# Power_Supply.net
KiCad netlist of a schematic drawn in Altium Designer
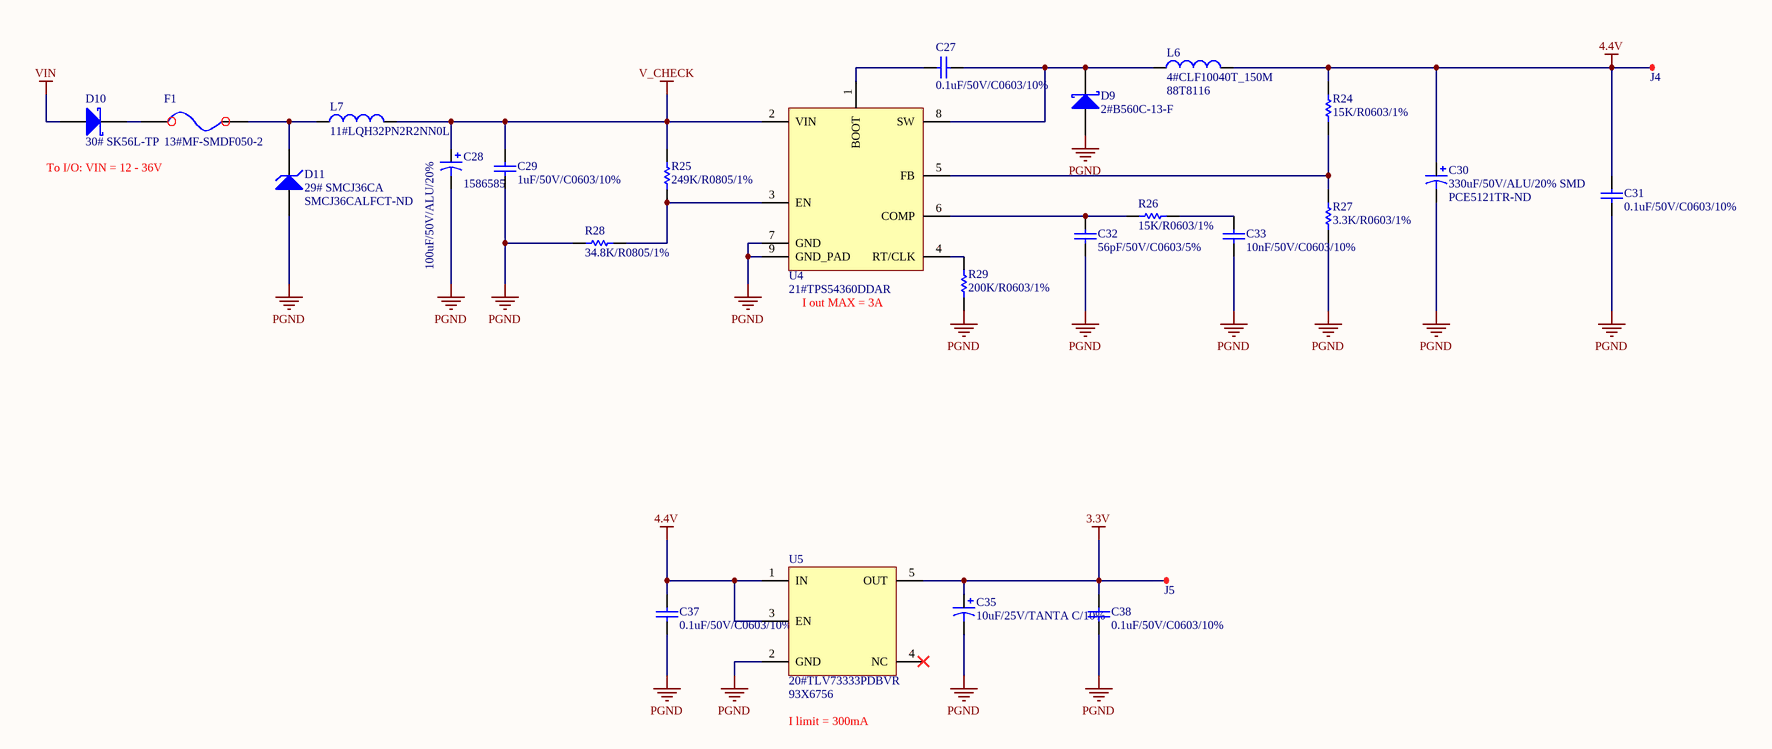
[diagram p0: Power Supply.SchDoc]

(export (version "E")
  (design (tool "Eeschema 10.0.6"))
  (components
    (comp (ref "C27")
      (value "0.1uF/50V/C0603/10%")
      (footprint "Cap Ceramic 0603 SMD")
      (description "CAP CER 0.1UF 50V 10% X7R 0603")
      (fields
        (field (name "MANUFACTURER") "Murata Electronics North America")
        (field (name "MANUFACTURER PART NUMBER") "GRM188R71H104KA93D")
      )
      (libsource (lib "GSHT_181013") (part "0.1uF/50V/C0603/10%"))
    )
    (comp (ref "C28")
      (value "100uF/50V/ALU/20%")
      (footprint "CAP ALU CASE F SMD")
      (description "CAP ALU 100UF 20% 50V RADIAL")
      (fields
        (field (name "MANUFACTURER") "Panasonic Electronic Components")
        (field (name "MANUFACTURER PART NUMBER") "ECA-1HM101B")
        (field (name "SUPPLIER PART NUMBER 1") "1586585")
      )
      (libsource (lib "GSHT_181013") (part "100uF/50V/ALU 8X11.5/20%"))
    )
    (comp (ref "C29")
      (value "1uF/50V/C0603/10%")
      (footprint "Cap Ceramic 0603 SMD")
      (description "CAP CER 1UF 50V X7R 0603")
      (fields
        (field (name "MANUFACTURER") "Samsung Electro-Mechanics America, Inc.")
        (field (name "MANUFACTURER PART NUMBER") "CL21B105KBFNNNE")
      )
      (libsource (lib "GSHT_181013") (part "1uF/50V/C0603/10%"))
    )
    (comp (ref "C30")
      (value "330uF/50V/ALU/20% SMD")
      (footprint "CAP ALU CASE G SMD")
      (description "CAP ALU 330UF 20% 50V SMD")
      (fields
        (field (name "MANUFACTURER") "Nichicon")
        (field (name "MANUFACTURER PART NUMBER") "UPW1J331MHD")
        (field (name "SUPPLIER PART NUMBER 1") "PCE5121TR-ND")
      )
      (libsource (lib "GSHT_181013") (part "330uF/50V/ALU12.5X20mm/20%/7000Hrs"))
    )
    (comp (ref "C31")
      (value "0.1uF/50V/C0603/10%")
      (footprint "Cap Ceramic 0603 SMD")
      (description "CAP CER 0.1UF 50V 10% X7R 0603")
      (fields
        (field (name "MANUFACTURER") "Murata Electronics North America")
        (field (name "MANUFACTURER PART NUMBER") "GRM188R71H104KA93D")
      )
      (libsource (lib "GSHT_181013") (part "0.1uF/50V/C0603/10%"))
    )
    (comp (ref "C32")
      (value "56pF/50V/C0603/5%")
      (footprint "Cap Ceramic 0603 SMD")
      (description "Cap Ceramic 56pF 50V C0G 5% SMD 0603 125C Paper T/R")
      (fields
        (field (name "MANUFACTURER") "Samsung")
        (field (name "MANUFACTURER PART NUMBER") "CL10C560JB8NNNC")
      )
      (libsource (lib "GSHT_181013") (part "56pF/50V/C0603/5%"))
    )
    (comp (ref "C33")
      (value "10nF/50V/C0603/10%")
      (footprint "Cap Ceramic 0603 SMD")
      (description "CAP CER 10000PF 50V X7R 0603")
      (fields
        (field (name "MANUFACTURER") "Murata Electronics North America")
        (field (name "MANUFACTURER PART NUMBER") "GRM188R71H103KA01D")
      )
      (libsource (lib "GSHT_181013") (part "10nF/50V/C0603/10%"))
    )
    (comp (ref "C35")
      (value "10uF/25V/TANTA C/10%")
      (footprint "CAP TANT CASE C SMD")
      (description "Tantalum Capacitors - Solid SMD 25v 10uF 20%Tol Code C")
      (fields
        (field (name "MANUFACTURER") "Kyocera AVX")
        (field (name "MANUFACTURER PART NUMBER") "TAJB106M025RNJ")
      )
      (libsource (lib "GSHT_181013") (part "TAJB106M025RNJ"))
    )
    (comp (ref "C37")
      (value "0.1uF/50V/C0603/10%")
      (footprint "Cap Ceramic 0603 SMD")
      (description "CAP CER 0.1UF 50V 10% X7R 0603")
      (fields
        (field (name "MANUFACTURER") "Murata Electronics North America")
        (field (name "MANUFACTURER PART NUMBER") "GRM188R71H104KA93D")
      )
      (libsource (lib "GSHT_181013") (part "0.1uF/50V/C0603/10%"))
    )
    (comp (ref "C38")
      (value "0.1uF/50V/C0603/10%")
      (footprint "Cap Ceramic 0603 SMD")
      (description "CAP CER 0.1UF 50V 10% X7R 0603")
      (fields
        (field (name "MANUFACTURER") "Murata Electronics North America")
        (field (name "MANUFACTURER PART NUMBER") "GRM188R71H104KA93D")
      )
      (libsource (lib "GSHT_181013") (part "0.1uF/50V/C0603/10%"))
    )
    (comp (ref "D9")
      (value "2#B560C-13-F")
      (footprint "2# B560C")
      (description "DIODE SCHOTTKY 60V 5A SMC")
      (fields (field (name "MANUFACTURER") "Diodes") (field (name "MANUFACTURER PART NUMBER") "B560C-13-F"))
      (libsource (lib "GSHT_181013") (part "2#B560C-13-F"))
    )
    (comp (ref "D10")
      (value "30# SK56L-TP")
      (footprint "30# SK56L-TPMSCT-ND")
      (description "DIODE SCHOTTKY 60V 5A")
      (fields
        (field (name "MANUFACTURER") "Micro Commercial Co")
        (field (name "MANUFACTURER PART NUMBER") "SK56L-TP")
      )
      (libsource (lib "GSHT_181013") (part "30# SK56L-TP"))
    )
    (comp (ref "D11")
      (value "29# SMCJ36CA")
      (footprint "29# diode SMCJ36A")
      (description "TVS DIODE 36VWM 58.1VC SMC")
      (fields
        (field (name "MANUFACTURER") "Littelfuse")
        (field (name "MANUFACTURER PART NUMBER") "SMCJ36CA")
        (field (name "SUPPLIER PART NUMBER 1") "SMCJ36CALFCT-ND")
      )
      (libsource (lib "GSHT_181013") (part "29# SMCJ36CA"))
    )
    (comp (ref "F1")
      (value "13#MF-SMDF050-2")
      (footprint "13# MF-SMDF050")
      (description "PTC RESETTABLE .55A 60V 2018")
      (fields (field (name "MANUFACTURER") "Bourns") (field (name "MANUFACTURER PART NUMBER") "MF-SMDF050-2"))
      (libsource (lib "GSHT_181013") (part "13#MF-SMDF050-2"))
    )
    (comp (ref "J4")
      (value "TEST POINT")
      (footprint "TEST POINT 1mm")
      (description "TPoint")
      (libsource (lib "GSHT_181013") (part "PAD 1mm"))
    )
    (comp (ref "J5")
      (value "TEST POINT")
      (footprint "TEST POINT 1mm")
      (description "TPoint")
      (libsource (lib "GSHT_181013") (part "PAD 1mm"))
    )
    (comp (ref "L6")
      (value "4#CLF10040T_150M")
      (footprint "4# clf10040XX")
      (description "FIXED IND 15uH 3.2A 40 MOHM (10.0×9.7×3.8)")
      (fields (field (name "SUPPLIER PART NUMBER 1") "88T8116"))
      (libsource (lib "GSHT_181013") (part "4#CLF10040T_150M"))
    )
    (comp (ref "L7")
      (value "11#LQH32PN2R2NN0L")
      (footprint "11# LQH32PN2R2")
      (description "Inductor Power Chip Shielded Wirewound 2.2uH 30% 1MHz Ferrite 1.6A 91.2mOhm DCR 1210 Embossed T/R")
      (fields
        (field (name "MANUFACTURER") "Murata")
        (field (name "MANUFACTURER PART NUMBER") "LQH32PN2R2NN0L")
      )
      (libsource (lib "GSHT_181013") (part "11#LQH32PN2R2NN0L"))
    )
    (comp (ref "R24")
      (value "15K/R0603/1%")
      (footprint "Res 0603 SMD")
      (description "RES SMD 15K OHM 1% 1/10W 0603")
      (fields
        (field (name "MANUFACTURER") "Yageo")
        (field (name "MANUFACTURER PART NUMBER") "RC0603FR-0715KL")
      )
      (libsource (lib "GSHT_181013") (part "15K/R0603/1%"))
    )
    (comp (ref "R25")
      (value "249K/R0805/1%")
      (footprint "Res 0805 SMD")
      (description "RES SMD 249K OHM 1% 1/10W 0805")
      (fields
        (field (name "MANUFACTURER") "Yageo")
        (field (name "MANUFACTURER PART NUMBER") "RC0603FR-07249KL")
      )
      (libsource (lib "GSHT_181013") (part "249K/R0805/1%"))
    )
    (comp (ref "R26")
      (value "15K/R0603/1%")
      (footprint "Res 0603 SMD")
      (description "RES SMD 15K OHM 1% 1/10W 0603")
      (fields
        (field (name "MANUFACTURER") "Yageo")
        (field (name "MANUFACTURER PART NUMBER") "RC0603FR-0715KL")
      )
      (libsource (lib "GSHT_181013") (part "15K/R0603/1%"))
    )
    (comp (ref "R27")
      (value "3.3K/R0603/1%")
      (footprint "Cap Ceramic 0603 SMD")
      (description "RES SMD 3.3K OHM 1% 1/10W 0603")
      (fields
        (field (name "MANUFACTURER") "Yageo")
        (field (name "MANUFACTURER PART NUMBER") "RC0603FR-073K3L")
      )
      (libsource (lib "GSHT_181013") (part "3.3K/R0603/1%"))
    )
    (comp (ref "R28")
      (value "34.8K/R0805/1%")
      (footprint "Res 0805 SMD")
      (description "Thick Film Resistors - SMD 34.8K OHM 1% 0805")
      (fields
        (field (name "MANUFACTURER") "Yageo")
        (field (name "MANUFACTURER PART NUMBER") "RC0603FR-0734K8L")
      )
      (libsource (lib "GSHT_181013") (part "34.8K/R0805/1%"))
    )
    (comp (ref "R29")
      (value "200K/R0603/1%")
      (footprint "Res 0603 SMD")
      (description "RES SMD 200K OHM 1% 1/10W 0603")
      (fields
        (field (name "MANUFACTURER") "Yageo")
        (field (name "MANUFACTURER PART NUMBER") "RC0603FR-07200KL")
      )
      (libsource (lib "GSHT_181013") (part "200K/R0603/1%"))
    )
    (comp (ref "U4")
      (value "21#TPS54360DDAR")
      (footprint "21# TPS54360")
      (description "Voltage Regulators - Switching Regulators 60 Vin,3.5 A,SD DC-DC Converter")
      (fields
        (field (name "MANUFACTURER") "Texas Instruments")
        (field (name "MANUFACTURER PART NUMBER") "TPS54360DDAR")
      )
      (libsource (lib "GSHT_181013") (part "21#TPS54360DDAR"))
    )
    (comp (ref "U5")
      (value "20#TLV73333PDBVR")
      (footprint "20# TLV73333PDBVR")
      (description "LDO Regulator Pos 3.3V 0.3A 5-Pin SOT-23 T/R")
      (fields
        (field (name "MANUFACTURER") "Texas Instruments")
        (field (name "MANUFACTURER PART NUMBER") "TLV73333PDBVR")
        (field (name "SUPPLIER PART NUMBER 1") "93X6756")
      )
      (libsource (lib "GSHT_181013") (part "20#TLV73333PDBVR"))
    )
  )
  (nets
    (net (code "1") (name "3.3V") (class "Default")
      (node (ref "C35") (pin "1") (pinfunction "1_1") (pintype "passive"))
      (node (ref "C38") (pin "2") (pinfunction "2_2") (pintype "passive"))
      (node (ref "J5") (pin "1") (pinfunction "TP_1") (pintype "passive"))
      (node (ref "U5") (pin "5") (pinfunction "OUT_5") (pintype "passive"))
    )
    (net (code "2") (name "4.4V") (class "Default")
      (node (ref "C30") (pin "1") (pinfunction "1_1") (pintype "passive"))
      (node (ref "C31") (pin "2") (pinfunction "2_2") (pintype "passive"))
      (node (ref "C37") (pin "2") (pinfunction "2_2") (pintype "passive"))
      (node (ref "J4") (pin "1") (pinfunction "TP_1") (pintype "passive"))
      (node (ref "L6") (pin "2") (pinfunction "2_2") (pintype "passive"))
      (node (ref "R24") (pin "2") (pinfunction "2_2") (pintype "passive"))
      (node (ref "U5") (pin "1") (pinfunction "IN_1") (pintype "passive"))
      (node (ref "U5") (pin "3") (pinfunction "EN_3") (pintype "passive"))
    )
    (net (code "3") (name "Net-(C33-Pad2)") (class "Default")
      (node (ref "C33") (pin "2") (pinfunction "2_2") (pintype "passive"))
      (node (ref "R26") (pin "1") (pinfunction "1_1") (pintype "passive"))
    )
    (net (code "4") (name "Net-(D9-K)") (class "Default")
      (node (ref "C27") (pin "2") (pinfunction "2_2") (pintype "passive"))
      (node (ref "D9") (pin "2") (pinfunction "K_2") (pintype "passive"))
      (node (ref "L6") (pin "1") (pinfunction "1_1") (pintype "passive"))
      (node (ref "U4") (pin "8") (pinfunction "SW_8") (pintype "passive"))
    )
    (net (code "5") (name "Net-(D10-K)") (class "Default")
      (node (ref "D10") (pin "2") (pinfunction "K_2") (pintype "passive"))
      (node (ref "F1") (pin "1") (pinfunction "IN_1") (pintype "passive"))
    )
    (net (code "6") (name "Net-(D11-K)") (class "Default")
      (node (ref "D11") (pin "2") (pinfunction "K_2") (pintype "passive"))
      (node (ref "F1") (pin "2") (pinfunction "OUT_2") (pintype "passive"))
      (node (ref "L7") (pin "1") (pinfunction "1_1") (pintype "passive"))
    )
    (net (code "7") (name "Net-(U4-BOOT)") (class "Default")
      (node (ref "C27") (pin "1") (pinfunction "1_1") (pintype "passive"))
      (node (ref "U4") (pin "1") (pinfunction "BOOT_1") (pintype "passive"))
    )
    (net (code "8") (name "Net-(U4-COMP)") (class "Default")
      (node (ref "C32") (pin "2") (pinfunction "2_2") (pintype "passive"))
      (node (ref "R26") (pin "2") (pinfunction "2_2") (pintype "passive"))
      (node (ref "U4") (pin "6") (pinfunction "COMP_6") (pintype "passive"))
    )
    (net (code "9") (name "Net-(U4-EN)") (class "Default")
      (node (ref "R25") (pin "1") (pinfunction "1_1") (pintype "passive"))
      (node (ref "R28") (pin "2") (pinfunction "2_2") (pintype "passive"))
      (node (ref "U4") (pin "3") (pinfunction "EN_3") (pintype "passive"))
    )
    (net (code "10") (name "Net-(U4-FB)") (class "Default")
      (node (ref "R24") (pin "1") (pinfunction "1_1") (pintype "passive"))
      (node (ref "R27") (pin "2") (pinfunction "2_2") (pintype "passive"))
      (node (ref "U4") (pin "5") (pinfunction "FB_5") (pintype "passive"))
    )
    (net (code "11") (name "Net-(U4-RT{slash}CLK)") (class "Default")
      (node (ref "R29") (pin "1") (pinfunction "1_1") (pintype "passive"))
      (node (ref "U4") (pin "4") (pinfunction "RT/CLK_4") (pintype "passive"))
    )
    (net (code "12") (name "PGND") (class "Default")
      (node (ref "C28") (pin "2") (pinfunction "2_2") (pintype "passive"))
      (node (ref "C29") (pin "1") (pinfunction "1_1") (pintype "passive"))
      (node (ref "C30") (pin "2") (pinfunction "2_2") (pintype "passive"))
      (node (ref "C31") (pin "1") (pinfunction "1_1") (pintype "passive"))
      (node (ref "C32") (pin "1") (pinfunction "1_1") (pintype "passive"))
      (node (ref "C33") (pin "1") (pinfunction "1_1") (pintype "passive"))
      (node (ref "C35") (pin "2") (pinfunction "2_2") (pintype "passive"))
      (node (ref "C37") (pin "1") (pinfunction "1_1") (pintype "passive"))
      (node (ref "C38") (pin "1") (pinfunction "1_1") (pintype "passive"))
      (node (ref "D11") (pin "1") (pinfunction "A_1") (pintype "passive"))
      (node (ref "D9") (pin "1") (pinfunction "A_1") (pintype "passive"))
      (node (ref "R27") (pin "1") (pinfunction "1_1") (pintype "passive"))
      (node (ref "R28") (pin "1") (pinfunction "1_1") (pintype "passive"))
      (node (ref "R29") (pin "2") (pinfunction "2_2") (pintype "passive"))
      (node (ref "U4") (pin "7") (pinfunction "GND_7") (pintype "passive"))
      (node (ref "U4") (pin "9") (pinfunction "GND_PAD_9") (pintype "passive"))
      (node (ref "U5") (pin "2") (pinfunction "GND_2") (pintype "passive"))
    )
    (net (code "13") (name "VIN") (class "Default")
      (node (ref "D10") (pin "1") (pinfunction "A_1") (pintype "passive"))
    )
    (net (code "14") (name "V_CHECK") (class "Default")
      (node (ref "C28") (pin "1") (pinfunction "1_1") (pintype "passive"))
      (node (ref "C29") (pin "2") (pinfunction "2_2") (pintype "passive"))
      (node (ref "L7") (pin "2") (pinfunction "2_2") (pintype "passive"))
      (node (ref "R25") (pin "2") (pinfunction "2_2") (pintype "passive"))
      (node (ref "U4") (pin "2") (pinfunction "VIN_2") (pintype "passive"))
    )
    (net (code "15") (name "unconnected-(U5-NC-Pad4)") (class "Default")
      (node (ref "U5") (pin "4") (pinfunction "NC_4") (pintype "passive+no_connect"))
    )
  )
)
